# easyeda_linefollower_planB.net
KiCad netlist of a schematic drawn in EasyEDA
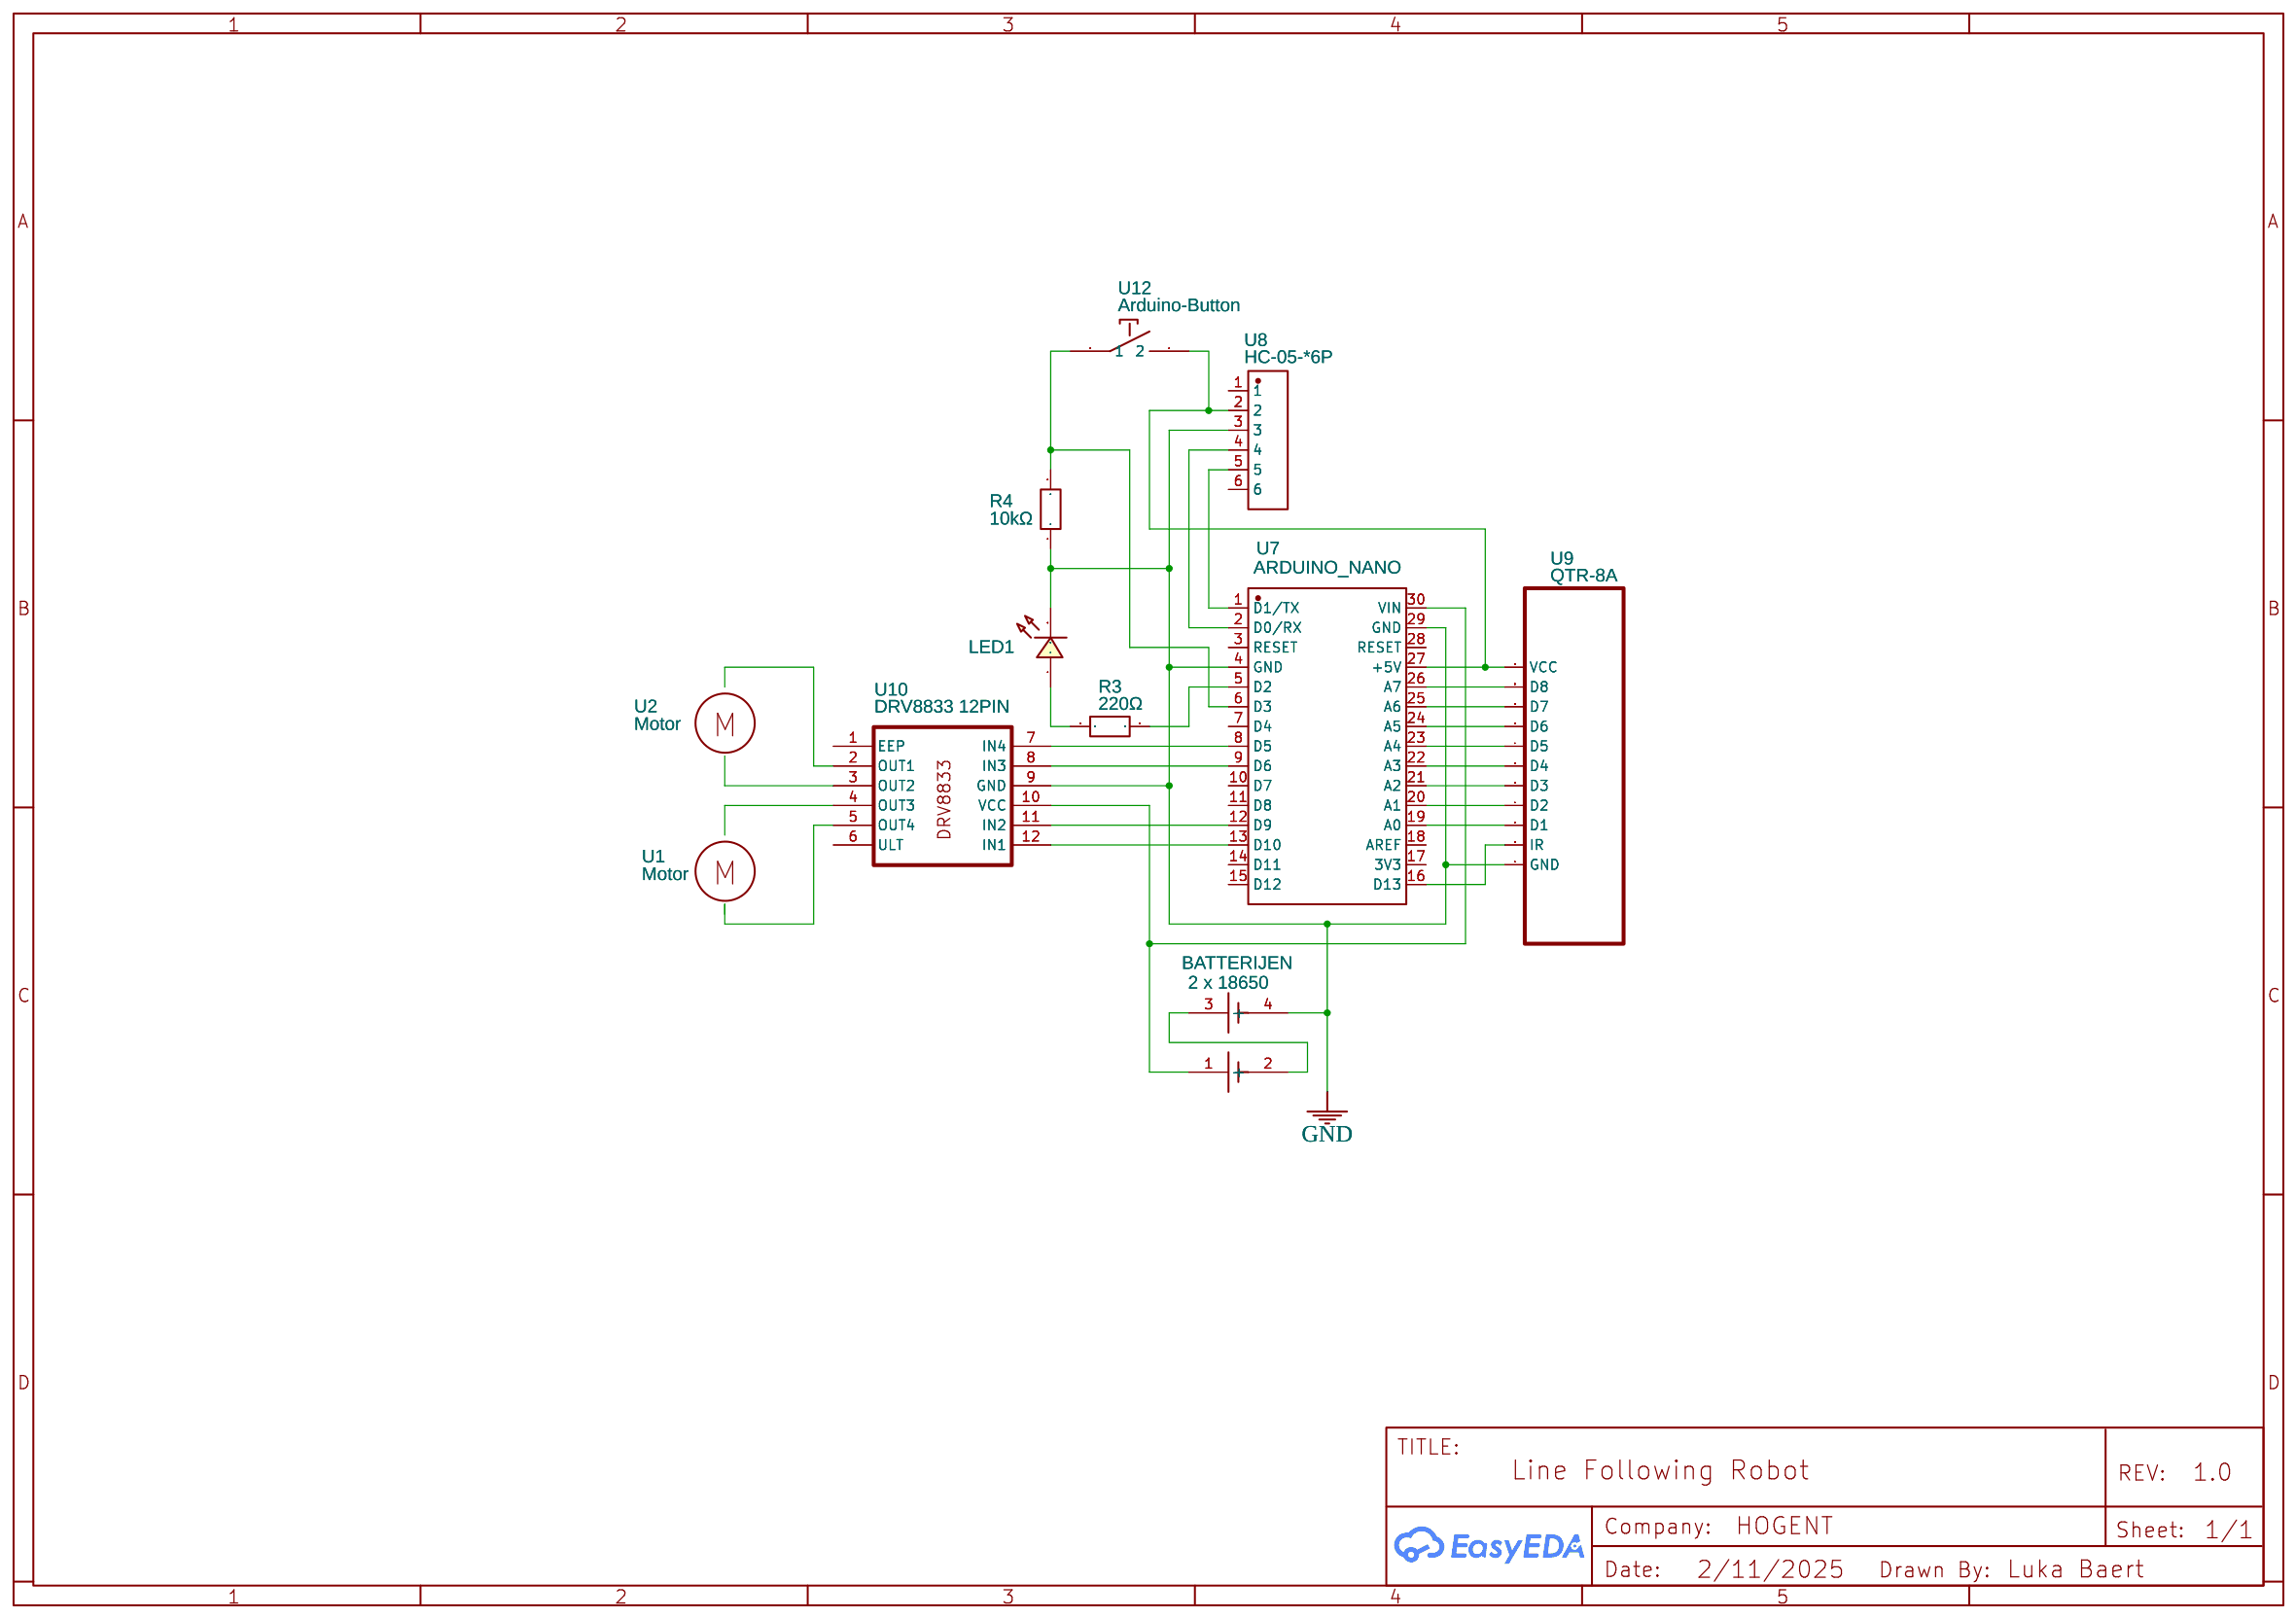
[diagram p0: schematic sheet]

(export (version "E")
  (design (tool "Eeschema 10.0.6"))
  (components
    (comp (ref "BATTERIJEN")
      (value "2 x 18650")
      (fields (field (name "Manufacturer Part") "BAT_X2_18650") (field (name "Manufacturer") "Dex"))
      (libsource (lib "") (part "BAT_X2_18650"))
    )
    (comp (ref "LED1")
      (value "LED-TH-5mm_R")
      (fields
        (field (name "Manufacturer Part") "333-2SURD/S530-A3")
        (field (name "Manufacturer") "EVERLIGHT(台湾亿光)")
      )
      (libsource (lib "") (part "LED-TH-5mm_R"))
    )
    (comp (ref "R3")
      (value "220Ω")
      (libsource (lib "") (part "AXIAL RESISTOR 220 OHM - TH_BD2.3-L6.0-P10.00-D0.4"))
    )
    (comp (ref "R4")
      (value "10kΩ")
      (libsource (lib "") (part "AXIAL RESISTOR 220 OHM - TH_BD2.3-L6.0-P10.00-D0.4_1"))
    )
    (comp (ref "U1") (value "Motor") (libsource (lib "") (part "Motor")))
    (comp (ref "U2") (value "Motor") (libsource (lib "") (part "Motor")))
    (comp (ref "U7") (value "ARDUINO_NANO") (libsource (lib "") (part "ARDUINO_NANO")))
    (comp (ref "U8")
      (value "HC-05-*6P")
      (fields (field (name "Manufacturer Part") "HC-05_排母*6P"))
      (libsource (lib "") (part "HC-05-*6P"))
    )
    (comp (ref "U9") (value "QTR-8A") (libsource (lib "") (part "QTR-8A")))
    (comp (ref "U10") (value "DRV8833 12PIN") (libsource (lib "") (part "DRV8833 12PIN")))
    (comp (ref "U12")
      (value "Arduino-Button")
      (fields (field (name "Manufacturer Part") "SW100664"))
      (libsource (lib "") (part "Arduino-Button"))
    )
  )
  (nets
    (net (code "1") (name "GND") (class "Default")
      (node (ref "BATTERIJEN") (pin "4") (pinfunction "-_4") (pintype "unspecified"))
      (node (ref "LED1") (pin "2") (pinfunction "2_2") (pintype "unspecified"))
      (node (ref "R4") (pin "1") (pinfunction "1_1") (pintype "unspecified"))
      (node (ref "U10") (pin "9") (pinfunction "GND_9") (pintype "unspecified"))
      (node (ref "U7") (pin "29") (pinfunction "GND_29") (pintype "unspecified"))
      (node (ref "U7") (pin "4") (pinfunction "GND_4") (pintype "unspecified"))
      (node (ref "U8") (pin "3") (pinfunction "3_3") (pintype "unspecified"))
      (node (ref "U9") (pin "1") (pinfunction "GND_1") (pintype "unspecified"))
    )
    (net (code "2") (name "Net-(BATTERIJEN-+-Pad3)") (class "Default")
      (node (ref "BATTERIJEN") (pin "2") (pinfunction "-_2") (pintype "unspecified"))
      (node (ref "BATTERIJEN") (pin "3") (pinfunction "+_3") (pintype "unspecified"))
    )
    (net (code "3") (name "Net-(LED1-Pad1)") (class "Default")
      (node (ref "LED1") (pin "1") (pinfunction "1_1") (pintype "unspecified"))
      (node (ref "R3") (pin "1") (pinfunction "1_1") (pintype "unspecified"))
    )
    (net (code "4") (name "Net-(U7-+5V)") (class "Default")
      (node (ref "U12") (pin "2") (pinfunction "2_2") (pintype "unspecified"))
      (node (ref "U7") (pin "27") (pinfunction "+5V_27") (pintype "unspecified"))
      (node (ref "U8") (pin "2") (pinfunction "2_2") (pintype "unspecified"))
      (node (ref "U9") (pin "11") (pinfunction "VCC_11") (pintype "unspecified"))
    )
    (net (code "5") (name "Net-(U7-A0)") (class "Default")
      (node (ref "U7") (pin "19") (pinfunction "A0_19") (pintype "unspecified"))
      (node (ref "U9") (pin "3") (pinfunction "D1_3") (pintype "unspecified"))
    )
    (net (code "6") (name "Net-(U7-A1)") (class "Default")
      (node (ref "U7") (pin "20") (pinfunction "A1_20") (pintype "unspecified"))
      (node (ref "U9") (pin "4") (pinfunction "D2_4") (pintype "unspecified"))
    )
    (net (code "7") (name "Net-(U7-A2)") (class "Default")
      (node (ref "U7") (pin "21") (pinfunction "A2_21") (pintype "unspecified"))
      (node (ref "U9") (pin "5") (pinfunction "D3_5") (pintype "unspecified"))
    )
    (net (code "8") (name "Net-(U7-A3)") (class "Default")
      (node (ref "U7") (pin "22") (pinfunction "A3_22") (pintype "unspecified"))
      (node (ref "U9") (pin "6") (pinfunction "D4_6") (pintype "unspecified"))
    )
    (net (code "9") (name "Net-(U7-A4)") (class "Default")
      (node (ref "U7") (pin "23") (pinfunction "A4_23") (pintype "unspecified"))
      (node (ref "U9") (pin "7") (pinfunction "D5_7") (pintype "unspecified"))
    )
    (net (code "10") (name "Net-(U7-A5)") (class "Default")
      (node (ref "U7") (pin "24") (pinfunction "A5_24") (pintype "unspecified"))
      (node (ref "U9") (pin "8") (pinfunction "D6_8") (pintype "unspecified"))
    )
    (net (code "11") (name "Net-(U7-A6)") (class "Default")
      (node (ref "U7") (pin "25") (pinfunction "A6_25") (pintype "unspecified"))
      (node (ref "U9") (pin "9") (pinfunction "D7_9") (pintype "unspecified"))
    )
    (net (code "12") (name "Net-(U7-A7)") (class "Default")
      (node (ref "U7") (pin "26") (pinfunction "A7_26") (pintype "unspecified"))
      (node (ref "U9") (pin "10") (pinfunction "D8_10") (pintype "unspecified"))
    )
    (net (code "13") (name "Net-(U7-D0{slash}RX)") (class "Default")
      (node (ref "U7") (pin "2") (pinfunction "D0/RX_2") (pintype "unspecified"))
      (node (ref "U8") (pin "4") (pinfunction "4_4") (pintype "unspecified"))
    )
    (net (code "14") (name "Net-(U7-D1{slash}TX)") (class "Default")
      (node (ref "U7") (pin "1") (pinfunction "D1/TX_1") (pintype "unspecified"))
      (node (ref "U8") (pin "5") (pinfunction "5_5") (pintype "unspecified"))
    )
    (net (code "15") (name "Net-(U7-D2)") (class "Default")
      (node (ref "R3") (pin "2") (pinfunction "2_2") (pintype "unspecified"))
      (node (ref "U7") (pin "5") (pinfunction "D2_5") (pintype "unspecified"))
    )
    (net (code "16") (name "Net-(U7-D3)") (class "Default")
      (node (ref "R4") (pin "2") (pinfunction "2_2") (pintype "unspecified"))
      (node (ref "U12") (pin "1") (pinfunction "1_1") (pintype "unspecified"))
      (node (ref "U7") (pin "6") (pinfunction "D3_6") (pintype "unspecified"))
    )
    (net (code "17") (name "Net-(U7-D13)") (class "Default")
      (node (ref "U7") (pin "16") (pinfunction "D13_16") (pintype "unspecified"))
      (node (ref "U9") (pin "2") (pinfunction "IR_2") (pintype "unspecified"))
    )
    (net (code "18") (name "Net-(U10-IN1)") (class "Default")
      (node (ref "U10") (pin "12") (pinfunction "IN1_12") (pintype "unspecified"))
      (node (ref "U7") (pin "13") (pinfunction "D10_13") (pintype "unspecified"))
    )
    (net (code "19") (name "Net-(U10-IN2)") (class "Default")
      (node (ref "U10") (pin "11") (pinfunction "IN2_11") (pintype "unspecified"))
      (node (ref "U7") (pin "12") (pinfunction "D9_12") (pintype "unspecified"))
    )
    (net (code "20") (name "Net-(U10-IN3)") (class "Default")
      (node (ref "U10") (pin "8") (pinfunction "IN3_8") (pintype "unspecified"))
      (node (ref "U7") (pin "9") (pinfunction "D6_9") (pintype "unspecified"))
    )
    (net (code "21") (name "Net-(U10-IN4)") (class "Default")
      (node (ref "U10") (pin "7") (pinfunction "IN4_7") (pintype "unspecified"))
      (node (ref "U7") (pin "8") (pinfunction "D5_8") (pintype "unspecified"))
    )
    (net (code "22") (name "Net-(U10-VCC)") (class "Default")
      (node (ref "BATTERIJEN") (pin "1") (pinfunction "+_1") (pintype "unspecified"))
      (node (ref "U10") (pin "10") (pinfunction "VCC_10") (pintype "unspecified"))
      (node (ref "U7") (pin "30") (pinfunction "VIN_30") (pintype "unspecified"))
    )
    (net (code "23") (name "unconnected-(U7-3V3-Pad17)") (class "Default")
      (node (ref "U7") (pin "17") (pinfunction "3V3_17") (pintype "unspecified"))
    )
    (net (code "24") (name "unconnected-(U7-AREF-Pad18)") (class "Default")
      (node (ref "U7") (pin "18") (pinfunction "AREF_18") (pintype "unspecified"))
    )
    (net (code "25") (name "unconnected-(U7-D4-Pad7)") (class "Default")
      (node (ref "U7") (pin "7") (pinfunction "D4_7") (pintype "unspecified"))
    )
    (net (code "26") (name "unconnected-(U7-D7-Pad10)") (class "Default")
      (node (ref "U7") (pin "10") (pinfunction "D7_10") (pintype "unspecified"))
    )
    (net (code "27") (name "unconnected-(U7-D8-Pad11)") (class "Default")
      (node (ref "U7") (pin "11") (pinfunction "D8_11") (pintype "unspecified"))
    )
    (net (code "28") (name "unconnected-(U7-D11-Pad14)") (class "Default")
      (node (ref "U7") (pin "14") (pinfunction "D11_14") (pintype "unspecified"))
    )
    (net (code "29") (name "unconnected-(U7-D12-Pad15)") (class "Default")
      (node (ref "U7") (pin "15") (pinfunction "D12_15") (pintype "unspecified"))
    )
    (net (code "30") (name "unconnected-(U7-RESET-Pad3)") (class "Default")
      (node (ref "U7") (pin "3") (pinfunction "RESET_3") (pintype "unspecified"))
    )
    (net (code "31") (name "unconnected-(U7-RESET-Pad28)") (class "Default")
      (node (ref "U7") (pin "28") (pinfunction "RESET_28") (pintype "unspecified"))
    )
    (net (code "32") (name "unconnected-(U8-Pad1)") (class "Default")
      (node (ref "U8") (pin "1") (pinfunction "1_1") (pintype "unspecified"))
    )
    (net (code "33") (name "unconnected-(U8-Pad6)") (class "Default")
      (node (ref "U8") (pin "6") (pinfunction "6_6") (pintype "unspecified"))
    )
    (net (code "34") (name "unconnected-(U10-EEP-Pad1)") (class "Default")
      (node (ref "U10") (pin "1") (pinfunction "EEP_1") (pintype "unspecified"))
    )
    (net (code "35") (name "unconnected-(U10-OUT1-Pad2)") (class "Default")
      (node (ref "U10") (pin "2") (pinfunction "OUT1_2") (pintype "unspecified"))
    )
    (net (code "36") (name "unconnected-(U10-OUT2-Pad3)") (class "Default")
      (node (ref "U10") (pin "3") (pinfunction "OUT2_3") (pintype "unspecified"))
    )
    (net (code "37") (name "unconnected-(U10-OUT3-Pad4)") (class "Default")
      (node (ref "U10") (pin "4") (pinfunction "OUT3_4") (pintype "unspecified"))
    )
    (net (code "38") (name "unconnected-(U10-OUT4-Pad5)") (class "Default")
      (node (ref "U10") (pin "5") (pinfunction "OUT4_5") (pintype "unspecified"))
    )
    (net (code "39") (name "unconnected-(U10-ULT-Pad6)") (class "Default")
      (node (ref "U10") (pin "6") (pinfunction "ULT_6") (pintype "unspecified"))
    )
  )
)
